# microcontroller.net
KiCad netlist of a schematic drawn in Altium Designer
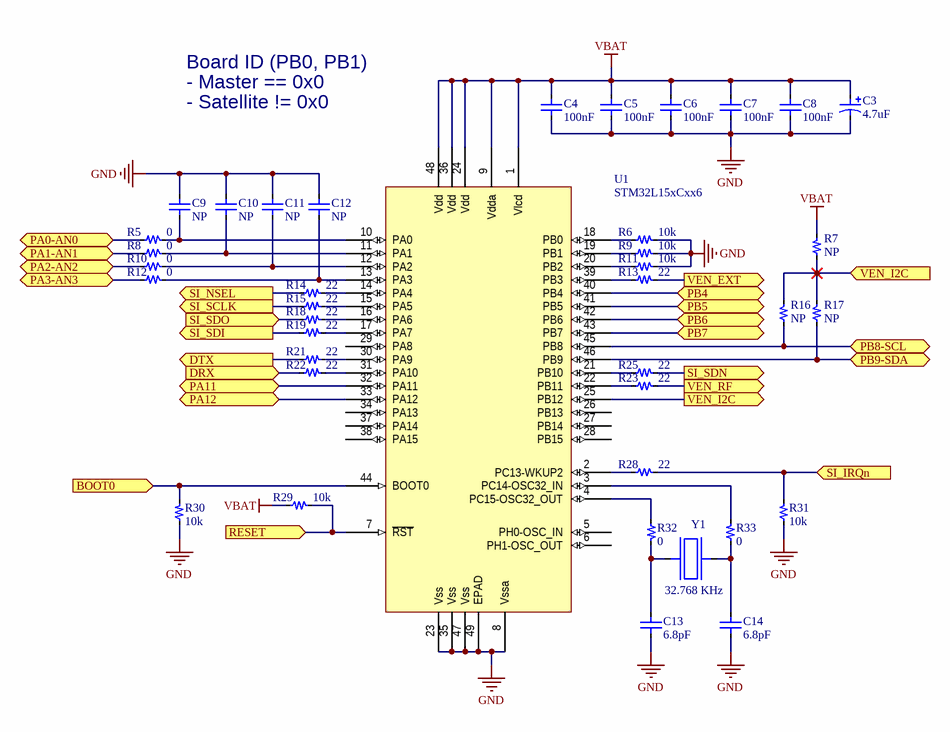
[diagram p0: microcontroller.SchDoc]

(export (version "E")
  (design (tool "Eeschema 10.0.6"))
  (components
    (comp (ref "C3")
      (value "4.7uF")
      (footprint "0603_[1608]")
      (description "Polarized capacitor")
      (libsource (lib "Discrete") (part "CPOL"))
    )
    (comp (ref "C4")
      (value "100nF")
      (footprint "0603_[1608]")
      (description "Capacitor")
      (libsource (lib "Discrete") (part "C"))
    )
    (comp (ref "C5")
      (value "100nF")
      (footprint "0603_[1608]")
      (description "Capacitor")
      (libsource (lib "Discrete") (part "C"))
    )
    (comp (ref "C6")
      (value "100nF")
      (footprint "0603_[1608]")
      (description "Capacitor")
      (libsource (lib "Discrete") (part "C"))
    )
    (comp (ref "C7")
      (value "100nF")
      (footprint "0603_[1608]")
      (description "Capacitor")
      (libsource (lib "Discrete") (part "C"))
    )
    (comp (ref "C8")
      (value "100nF")
      (footprint "0603_[1608]")
      (description "Capacitor")
      (libsource (lib "Discrete") (part "C"))
    )
    (comp (ref "C9")
      (value "NP")
      (footprint "0603_[1608]")
      (description "Capacitor")
      (libsource (lib "Discrete") (part "C"))
    )
    (comp (ref "C10")
      (value "NP")
      (footprint "0603_[1608]")
      (description "Capacitor")
      (libsource (lib "Discrete") (part "C"))
    )
    (comp (ref "C11")
      (value "NP")
      (footprint "0603_[1608]")
      (description "Capacitor")
      (libsource (lib "Discrete") (part "C"))
    )
    (comp (ref "C12")
      (value "NP")
      (footprint "0603_[1608]")
      (description "Capacitor")
      (libsource (lib "Discrete") (part "C"))
    )
    (comp (ref "C13")
      (value "6.8pF")
      (footprint "0603_[1608]")
      (description "Capacitor")
      (libsource (lib "Discrete") (part "C"))
    )
    (comp (ref "C14")
      (value "6.8pF")
      (footprint "0603_[1608]")
      (description "Capacitor")
      (libsource (lib "Discrete") (part "C"))
    )
    (comp (ref "R5")
      (value "0")
      (footprint "0603_[1608]")
      (description "Resistor")
      (libsource (lib "Discrete") (part "R"))
    )
    (comp (ref "R6")
      (value "10k")
      (footprint "0603_[1608]")
      (description "Resistor")
      (libsource (lib "Discrete") (part "R"))
    )
    (comp (ref "R7")
      (value "NP")
      (footprint "0603_[1608]")
      (description "Resistor")
      (libsource (lib "Discrete") (part "R"))
    )
    (comp (ref "R8")
      (value "0")
      (footprint "0603_[1608]")
      (description "Resistor")
      (libsource (lib "Discrete") (part "R"))
    )
    (comp (ref "R9")
      (value "10k")
      (footprint "0603_[1608]")
      (description "Resistor")
      (libsource (lib "Discrete") (part "R"))
    )
    (comp (ref "R10")
      (value "0")
      (footprint "0603_[1608]")
      (description "Resistor")
      (libsource (lib "Discrete") (part "R"))
    )
    (comp (ref "R11")
      (value "10k")
      (footprint "0603_[1608]")
      (description "Resistor")
      (libsource (lib "Discrete") (part "R"))
    )
    (comp (ref "R12")
      (value "0")
      (footprint "0603_[1608]")
      (description "Resistor")
      (libsource (lib "Discrete") (part "R"))
    )
    (comp (ref "R13")
      (value "22")
      (footprint "0603_[1608]")
      (description "Resistor")
      (libsource (lib "Discrete") (part "R"))
    )
    (comp (ref "R14")
      (value "22")
      (footprint "0603_[1608]")
      (description "Resistor")
      (libsource (lib "Discrete") (part "R"))
    )
    (comp (ref "R15")
      (value "22")
      (footprint "0603_[1608]")
      (description "Resistor")
      (libsource (lib "Discrete") (part "R"))
    )
    (comp (ref "R16")
      (value "NP")
      (footprint "0603_[1608]")
      (description "Resistor")
      (libsource (lib "Discrete") (part "R"))
    )
    (comp (ref "R17")
      (value "NP")
      (footprint "0603_[1608]")
      (description "Resistor")
      (libsource (lib "Discrete") (part "R"))
    )
    (comp (ref "R18")
      (value "22")
      (footprint "0603_[1608]")
      (description "Resistor")
      (libsource (lib "Discrete") (part "R"))
    )
    (comp (ref "R19")
      (value "22")
      (footprint "0603_[1608]")
      (description "Resistor")
      (libsource (lib "Discrete") (part "R"))
    )
    (comp (ref "R21")
      (value "22")
      (footprint "0603_[1608]")
      (description "Resistor")
      (libsource (lib "Discrete") (part "R"))
    )
    (comp (ref "R22")
      (value "22")
      (footprint "0603_[1608]")
      (description "Resistor")
      (libsource (lib "Discrete") (part "R"))
    )
    (comp (ref "R23")
      (value "22")
      (footprint "0603_[1608]")
      (description "Resistor")
      (libsource (lib "Discrete") (part "R"))
    )
    (comp (ref "R25")
      (value "22")
      (footprint "0603_[1608]")
      (description "Resistor")
      (libsource (lib "Discrete") (part "R"))
    )
    (comp (ref "R28")
      (value "22")
      (footprint "0603_[1608]")
      (description "Resistor")
      (libsource (lib "Discrete") (part "R"))
    )
    (comp (ref "R29")
      (value "10k")
      (footprint "0603_[1608]")
      (description "Resistor")
      (libsource (lib "Discrete") (part "R"))
    )
    (comp (ref "R30")
      (value "10k")
      (footprint "0603_[1608]")
      (description "Resistor")
      (libsource (lib "Discrete") (part "R"))
    )
    (comp (ref "R31")
      (value "10k")
      (footprint "0603_[1608]")
      (description "Resistor")
      (libsource (lib "Discrete") (part "R"))
    )
    (comp (ref "R32")
      (value "0")
      (footprint "0603_[1608]")
      (description "Resistor")
      (libsource (lib "Discrete") (part "R"))
    )
    (comp (ref "R33")
      (value "0")
      (footprint "0603_[1608]")
      (description "Resistor")
      (libsource (lib "Discrete") (part "R"))
    )
    (comp (ref "U1")
      (value "STM32L15xCxx6")
      (footprint "QFN50P700X700X60_HS-49N")
      (libsource (lib "Microcontrollers") (part "STM32L15xCxx6"))
    )
    (comp (ref "Y1")
      (value "32.768 KHz")
      (footprint "KX-38")
      (description "Crystal oscillator")
      (libsource (lib "Discrete") (part "XTAL"))
    )
  )
  (nets
    (net (code "1") (name "/BOOT0") (class "Default")
      (node (ref "R30") (pin "2") (pinfunction "2_2") (pintype "passive"))
      (node (ref "U1") (pin "44") (pinfunction "BOOT0_44") (pintype "input"))
    )
    (net (code "2") (name "/DRX") (class "Default")
      (node (ref "R22") (pin "1") (pinfunction "1_1") (pintype "passive"))
    )
    (net (code "3") (name "/DTX") (class "Default")
      (node (ref "R21") (pin "1") (pinfunction "1_1") (pintype "passive"))
    )
    (net (code "4") (name "/PA0-AN0") (class "Default")
      (node (ref "R5") (pin "1") (pinfunction "1_1") (pintype "passive"))
    )
    (net (code "5") (name "/PA1-AN1") (class "Default")
      (node (ref "R8") (pin "1") (pinfunction "1_1") (pintype "passive"))
    )
    (net (code "6") (name "/PA2-AN2") (class "Default")
      (node (ref "R10") (pin "1") (pinfunction "1_1") (pintype "passive"))
    )
    (net (code "7") (name "/PA3-AN3") (class "Default")
      (node (ref "R12") (pin "1") (pinfunction "1_1") (pintype "passive"))
    )
    (net (code "8") (name "/PA11") (class "Default")
      (node (ref "U1") (pin "32") (pinfunction "PA11_32") (pintype "bidirectional"))
    )
    (net (code "9") (name "/PA12") (class "Default")
      (node (ref "U1") (pin "33") (pinfunction "PA12_33") (pintype "bidirectional"))
    )
    (net (code "10") (name "/PB4") (class "Default")
      (node (ref "U1") (pin "40") (pinfunction "PB4_40") (pintype "bidirectional"))
    )
    (net (code "11") (name "/PB5") (class "Default")
      (node (ref "U1") (pin "41") (pinfunction "PB5_41") (pintype "bidirectional"))
    )
    (net (code "12") (name "/PB6") (class "Default")
      (node (ref "U1") (pin "42") (pinfunction "PB6_42") (pintype "bidirectional"))
    )
    (net (code "13") (name "/PB7") (class "Default")
      (node (ref "U1") (pin "43") (pinfunction "PB7_43") (pintype "bidirectional"))
    )
    (net (code "14") (name "/PB8-SCL") (class "Default")
      (node (ref "R16") (pin "1") (pinfunction "1_1") (pintype "passive"))
      (node (ref "U1") (pin "45") (pinfunction "PB8_45") (pintype "bidirectional"))
    )
    (net (code "15") (name "/PB9-SDA") (class "Default")
      (node (ref "R17") (pin "1") (pinfunction "1_1") (pintype "passive"))
      (node (ref "U1") (pin "46") (pinfunction "PB9_46") (pintype "bidirectional"))
    )
    (net (code "16") (name "/RESET") (class "Default")
      (node (ref "R29") (pin "2") (pinfunction "2_2") (pintype "passive"))
      (node (ref "U1") (pin "7") (pinfunction "~{RST}_7") (pintype "input"))
    )
    (net (code "17") (name "/SI_IRQn") (class "Default")
      (node (ref "R28") (pin "2") (pinfunction "2_2") (pintype "passive"))
      (node (ref "R31") (pin "2") (pinfunction "2_2") (pintype "passive"))
    )
    (net (code "18") (name "/SI_NSEL") (class "Default")
      (node (ref "R14") (pin "1") (pinfunction "1_1") (pintype "passive"))
    )
    (net (code "19") (name "/SI_SCLK") (class "Default")
      (node (ref "R15") (pin "1") (pinfunction "1_1") (pintype "passive"))
    )
    (net (code "20") (name "/SI_SDI") (class "Default")
      (node (ref "R19") (pin "1") (pinfunction "1_1") (pintype "passive"))
    )
    (net (code "21") (name "/SI_SDN") (class "Default")
      (node (ref "R25") (pin "2") (pinfunction "2_2") (pintype "passive"))
    )
    (net (code "22") (name "/SI_SDO") (class "Default")
      (node (ref "R18") (pin "1") (pinfunction "1_1") (pintype "passive"))
    )
    (net (code "23") (name "/VEN_EXT") (class "Default")
      (node (ref "R13") (pin "2") (pinfunction "2_2") (pintype "passive"))
    )
    (net (code "24") (name "/VEN_I2C") (class "Default")
      (node (ref "R16") (pin "2") (pinfunction "2_2") (pintype "passive"))
      (node (ref "R17") (pin "2") (pinfunction "2_2") (pintype "passive"))
      (node (ref "R7") (pin "1") (pinfunction "1_1") (pintype "passive"))
      (node (ref "U1") (pin "25") (pinfunction "PB12_25") (pintype "bidirectional"))
    )
    (net (code "25") (name "/VEN_RF") (class "Default")
      (node (ref "R23") (pin "2") (pinfunction "2_2") (pintype "passive"))
    )
    (net (code "26") (name "GND") (class "Default")
      (node (ref "C10") (pin "2") (pinfunction "2_2") (pintype "passive"))
      (node (ref "C11") (pin "2") (pinfunction "2_2") (pintype "passive"))
      (node (ref "C12") (pin "2") (pinfunction "2_2") (pintype "passive"))
      (node (ref "C13") (pin "1") (pinfunction "1_1") (pintype "passive"))
      (node (ref "C14") (pin "1") (pinfunction "1_1") (pintype "passive"))
      (node (ref "C3") (pin "2") (pinfunction "2_2") (pintype "passive"))
      (node (ref "C4") (pin "1") (pinfunction "1_1") (pintype "passive"))
      (node (ref "C5") (pin "1") (pinfunction "1_1") (pintype "passive"))
      (node (ref "C6") (pin "1") (pinfunction "1_1") (pintype "passive"))
      (node (ref "C7") (pin "1") (pinfunction "1_1") (pintype "passive"))
      (node (ref "C8") (pin "1") (pinfunction "1_1") (pintype "passive"))
      (node (ref "C9") (pin "2") (pinfunction "2_2") (pintype "passive"))
      (node (ref "R11") (pin "2") (pinfunction "2_2") (pintype "passive"))
      (node (ref "R30") (pin "1") (pinfunction "1_1") (pintype "passive"))
      (node (ref "R31") (pin "1") (pinfunction "1_1") (pintype "passive"))
      (node (ref "R6") (pin "2") (pinfunction "2_2") (pintype "passive"))
      (node (ref "R9") (pin "2") (pinfunction "2_2") (pintype "passive"))
      (node (ref "U1") (pin "23") (pinfunction "Vss_23") (pintype "power_in"))
      (node (ref "U1") (pin "35") (pinfunction "Vss_35") (pintype "power_in"))
      (node (ref "U1") (pin "47") (pinfunction "Vss_47") (pintype "power_in"))
      (node (ref "U1") (pin "49") (pinfunction "EPAD_49") (pintype "power_in"))
      (node (ref "U1") (pin "8") (pinfunction "Vssa_8") (pintype "power_in"))
    )
    (net (code "27") (name "Net-(C13-Pad2)") (class "Default")
      (node (ref "C13") (pin "2") (pinfunction "2_2") (pintype "passive"))
      (node (ref "R32") (pin "2") (pinfunction "2_2") (pintype "passive"))
      (node (ref "Y1") (pin "1") (pinfunction "1_1") (pintype "passive"))
    )
    (net (code "28") (name "Net-(C14-Pad2)") (class "Default")
      (node (ref "C14") (pin "2") (pinfunction "2_2") (pintype "passive"))
      (node (ref "R33") (pin "1") (pinfunction "1_1") (pintype "passive"))
      (node (ref "Y1") (pin "2") (pinfunction "2_2") (pintype "passive"))
    )
    (net (code "29") (name "Net-(U1-PA0)") (class "Default")
      (node (ref "C9") (pin "1") (pinfunction "1_1") (pintype "passive"))
      (node (ref "R5") (pin "2") (pinfunction "2_2") (pintype "passive"))
      (node (ref "U1") (pin "10") (pinfunction "PA0_10") (pintype "bidirectional"))
    )
    (net (code "30") (name "Net-(U1-PA1)") (class "Default")
      (node (ref "C10") (pin "1") (pinfunction "1_1") (pintype "passive"))
      (node (ref "R8") (pin "2") (pinfunction "2_2") (pintype "passive"))
      (node (ref "U1") (pin "11") (pinfunction "PA1_11") (pintype "bidirectional"))
    )
    (net (code "31") (name "Net-(U1-PA2)") (class "Default")
      (node (ref "C11") (pin "1") (pinfunction "1_1") (pintype "passive"))
      (node (ref "R10") (pin "2") (pinfunction "2_2") (pintype "passive"))
      (node (ref "U1") (pin "12") (pinfunction "PA2_12") (pintype "bidirectional"))
    )
    (net (code "32") (name "Net-(U1-PA3)") (class "Default")
      (node (ref "C12") (pin "1") (pinfunction "1_1") (pintype "passive"))
      (node (ref "R12") (pin "2") (pinfunction "2_2") (pintype "passive"))
      (node (ref "U1") (pin "13") (pinfunction "PA3_13") (pintype "bidirectional"))
    )
    (net (code "33") (name "Net-(U1-PA4)") (class "Default")
      (node (ref "R14") (pin "2") (pinfunction "2_2") (pintype "passive"))
      (node (ref "U1") (pin "14") (pinfunction "PA4_14") (pintype "bidirectional"))
    )
    (net (code "34") (name "Net-(U1-PA5)") (class "Default")
      (node (ref "R15") (pin "2") (pinfunction "2_2") (pintype "passive"))
      (node (ref "U1") (pin "15") (pinfunction "PA5_15") (pintype "bidirectional"))
    )
    (net (code "35") (name "Net-(U1-PA6)") (class "Default")
      (node (ref "R18") (pin "2") (pinfunction "2_2") (pintype "passive"))
      (node (ref "U1") (pin "16") (pinfunction "PA6_16") (pintype "bidirectional"))
    )
    (net (code "36") (name "Net-(U1-PA7)") (class "Default")
      (node (ref "R19") (pin "2") (pinfunction "2_2") (pintype "passive"))
      (node (ref "U1") (pin "17") (pinfunction "PA7_17") (pintype "bidirectional"))
    )
    (net (code "37") (name "Net-(U1-PA9)") (class "Default")
      (node (ref "R21") (pin "2") (pinfunction "2_2") (pintype "passive"))
      (node (ref "U1") (pin "30") (pinfunction "PA9_30") (pintype "bidirectional"))
    )
    (net (code "38") (name "Net-(U1-PA10)") (class "Default")
      (node (ref "R22") (pin "2") (pinfunction "2_2") (pintype "passive"))
      (node (ref "U1") (pin "31") (pinfunction "PA10_31") (pintype "bidirectional"))
    )
    (net (code "39") (name "Net-(U1-PB0)") (class "Default")
      (node (ref "R6") (pin "1") (pinfunction "1_1") (pintype "passive"))
      (node (ref "U1") (pin "18") (pinfunction "PB0_18") (pintype "bidirectional"))
    )
    (net (code "40") (name "Net-(U1-PB1)") (class "Default")
      (node (ref "R9") (pin "1") (pinfunction "1_1") (pintype "passive"))
      (node (ref "U1") (pin "19") (pinfunction "PB1_19") (pintype "bidirectional"))
    )
    (net (code "41") (name "Net-(U1-PB2)") (class "Default")
      (node (ref "R11") (pin "1") (pinfunction "1_1") (pintype "passive"))
      (node (ref "U1") (pin "20") (pinfunction "PB2_20") (pintype "bidirectional"))
    )
    (net (code "42") (name "Net-(U1-PB3)") (class "Default")
      (node (ref "R13") (pin "1") (pinfunction "1_1") (pintype "passive"))
      (node (ref "U1") (pin "39") (pinfunction "PB3_39") (pintype "bidirectional"))
    )
    (net (code "43") (name "Net-(U1-PB10)") (class "Default")
      (node (ref "R25") (pin "1") (pinfunction "1_1") (pintype "passive"))
      (node (ref "U1") (pin "21") (pinfunction "PB10_21") (pintype "bidirectional"))
    )
    (net (code "44") (name "Net-(U1-PB11)") (class "Default")
      (node (ref "R23") (pin "1") (pinfunction "1_1") (pintype "passive"))
      (node (ref "U1") (pin "22") (pinfunction "PB11_22") (pintype "bidirectional"))
    )
    (net (code "45") (name "Net-(U1-PC13-WKUP2)") (class "Default")
      (node (ref "R28") (pin "1") (pinfunction "1_1") (pintype "passive"))
      (node (ref "U1") (pin "2") (pinfunction "PC13-WKUP2_2") (pintype "bidirectional"))
    )
    (net (code "46") (name "Net-(U1-PC14-OSC32_IN)") (class "Default")
      (node (ref "R33") (pin "2") (pinfunction "2_2") (pintype "passive"))
      (node (ref "U1") (pin "3") (pinfunction "PC14-OSC32_IN_3") (pintype "bidirectional"))
    )
    (net (code "47") (name "Net-(U1-PC15-OSC32_OUT)") (class "Default")
      (node (ref "R32") (pin "1") (pinfunction "1_1") (pintype "passive"))
      (node (ref "U1") (pin "4") (pinfunction "PC15-OSC32_OUT_4") (pintype "bidirectional"))
    )
    (net (code "48") (name "VBAT") (class "Default")
      (node (ref "C3") (pin "1") (pinfunction "1_1") (pintype "passive"))
      (node (ref "C4") (pin "2") (pinfunction "2_2") (pintype "passive"))
      (node (ref "C5") (pin "2") (pinfunction "2_2") (pintype "passive"))
      (node (ref "C6") (pin "2") (pinfunction "2_2") (pintype "passive"))
      (node (ref "C7") (pin "2") (pinfunction "2_2") (pintype "passive"))
      (node (ref "C8") (pin "2") (pinfunction "2_2") (pintype "passive"))
      (node (ref "R29") (pin "1") (pinfunction "1_1") (pintype "passive"))
      (node (ref "R7") (pin "2") (pinfunction "2_2") (pintype "passive"))
      (node (ref "U1") (pin "1") (pinfunction "Vlcd_1") (pintype "power_in"))
      (node (ref "U1") (pin "24") (pinfunction "Vdd_24") (pintype "power_in"))
      (node (ref "U1") (pin "36") (pinfunction "Vdd_36") (pintype "power_in"))
      (node (ref "U1") (pin "48") (pinfunction "Vdd_48") (pintype "power_in"))
      (node (ref "U1") (pin "9") (pinfunction "Vdda_9") (pintype "power_in"))
    )
    (net (code "49") (name "unconnected-(U1-PA8-Pad29)") (class "Default")
      (node (ref "U1") (pin "29") (pinfunction "PA8_29") (pintype "bidirectional"))
    )
    (net (code "50") (name "unconnected-(U1-PA13-Pad34)") (class "Default")
      (node (ref "U1") (pin "34") (pinfunction "PA13_34") (pintype "bidirectional"))
    )
    (net (code "51") (name "unconnected-(U1-PA14-Pad37)") (class "Default")
      (node (ref "U1") (pin "37") (pinfunction "PA14_37") (pintype "bidirectional"))
    )
    (net (code "52") (name "unconnected-(U1-PA15-Pad38)") (class "Default")
      (node (ref "U1") (pin "38") (pinfunction "PA15_38") (pintype "bidirectional"))
    )
    (net (code "53") (name "unconnected-(U1-PB13-Pad26)") (class "Default")
      (node (ref "U1") (pin "26") (pinfunction "PB13_26") (pintype "bidirectional"))
    )
    (net (code "54") (name "unconnected-(U1-PB14-Pad27)") (class "Default")
      (node (ref "U1") (pin "27") (pinfunction "PB14_27") (pintype "bidirectional"))
    )
    (net (code "55") (name "unconnected-(U1-PB15-Pad28)") (class "Default")
      (node (ref "U1") (pin "28") (pinfunction "PB15_28") (pintype "bidirectional"))
    )
    (net (code "56") (name "unconnected-(U1-PH0-OSC_IN-Pad5)") (class "Default")
      (node (ref "U1") (pin "5") (pinfunction "PH0-OSC_IN_5") (pintype "bidirectional"))
    )
    (net (code "57") (name "unconnected-(U1-PH1-OSC_OUT-Pad6)") (class "Default")
      (node (ref "U1") (pin "6") (pinfunction "PH1-OSC_OUT_6") (pintype "bidirectional"))
    )
  )
)
